# picboard.net
KiCad netlist of a schematic drawn in EAGLE
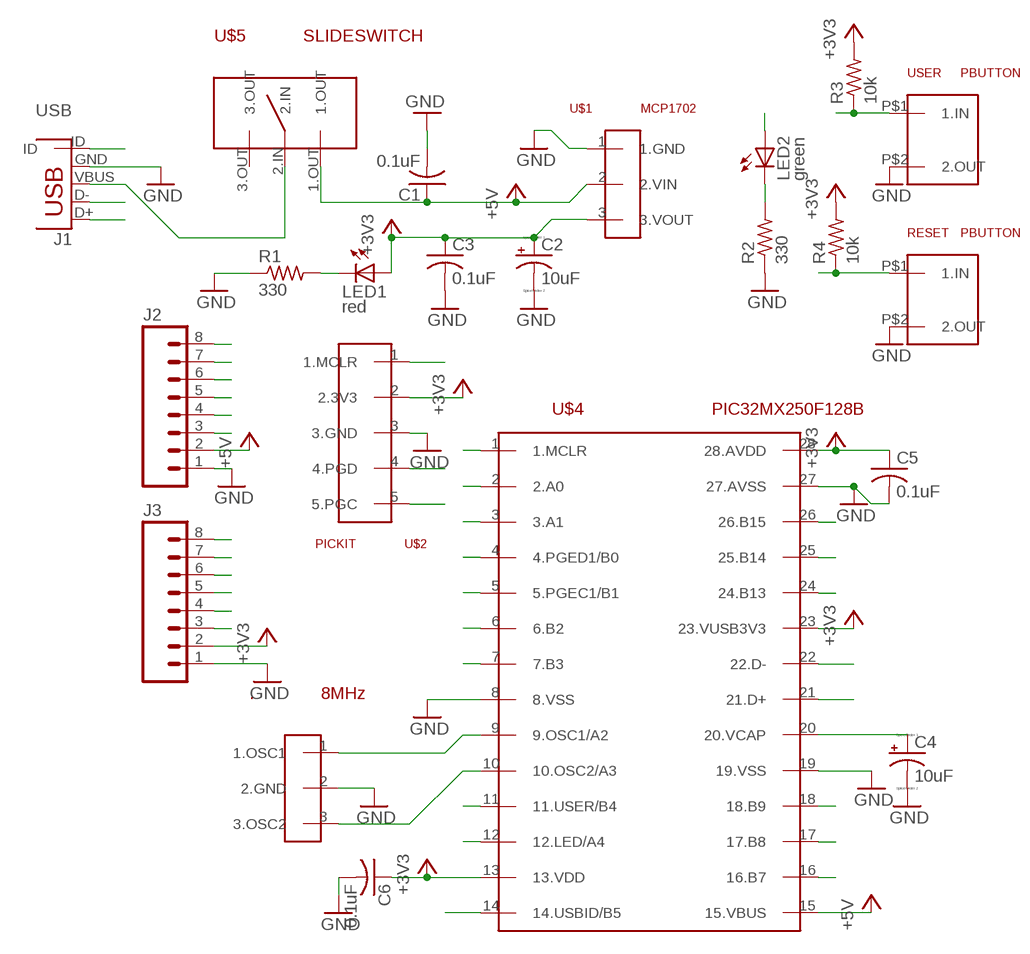
[diagram p0: schematic, sheet 1]

(export (version "E")
  (design (tool "Eeschema 10.0.6"))
  (components
    (comp (ref ".")
      (value "8MHz")
      (footprint "eagle-import:1X03")
      (libsource (lib "eagle-import") (part "OSCIL"))
    )
    (comp (ref "C1")
      (value "0.1uF")
      (footprint "eagle-import:C025-025X050")
      (libsource (lib "eagle-import") (part "C-US025-025X050"))
    )
    (comp (ref "C2")
      (value "10uF")
      (footprint "eagle-import:B45181A")
      (libsource (lib "eagle-import") (part "CPOL-USB45181A"))
    )
    (comp (ref "C3")
      (value "0.1uF")
      (footprint "eagle-import:C025-025X050")
      (libsource (lib "eagle-import") (part "C-US025-025X050"))
    )
    (comp (ref "C4")
      (value "10uF")
      (footprint "eagle-import:B45181A")
      (libsource (lib "eagle-import") (part "CPOL-USB45181A"))
    )
    (comp (ref "C5")
      (value "0.1uF")
      (footprint "eagle-import:C025-025X050")
      (libsource (lib "eagle-import") (part "C-US025-025X050"))
    )
    (comp (ref "C6")
      (value "0.1uF")
      (footprint "eagle-import:C025-025X050")
      (libsource (lib "eagle-import") (part "C-US025-025X050"))
    )
    (comp (ref "J1")
      (value "USB")
      (footprint "eagle-import:USB-MB-H")
      (libsource (lib "eagle-import") (part "USB"))
    )
    (comp (ref "J2")
      (value "M08")
      (footprint "eagle-import:1X08_ROUND")
      (libsource (lib "eagle-import") (part "M08"))
    )
    (comp (ref "J3")
      (value "M08")
      (footprint "eagle-import:1X08_ROUND")
      (libsource (lib "eagle-import") (part "M08"))
    )
    (comp (ref "LED1")
      (value "red")
      (footprint "eagle-import:LED3MM")
      (libsource (lib "eagle-import") (part "LED3MM"))
    )
    (comp (ref "LED2")
      (value "green")
      (footprint "eagle-import:LED3MM")
      (libsource (lib "eagle-import") (part "LED3MM"))
    )
    (comp (ref "R1")
      (value "330")
      (footprint "eagle-import:0207_10")
      (libsource (lib "eagle-import") (part "R-US_0207/10"))
    )
    (comp (ref "R2")
      (value "330")
      (footprint "eagle-import:0207_10")
      (libsource (lib "eagle-import") (part "R-US_0207/10"))
    )
    (comp (ref "R3")
      (value "10k")
      (footprint "eagle-import:0207_10")
      (libsource (lib "eagle-import") (part "R-US_0207/10"))
    )
    (comp (ref "R4")
      (value "10k")
      (footprint "eagle-import:0207_10")
      (libsource (lib "eagle-import") (part "R-US_0207/10"))
    )
    (comp (ref "RESET")
      (value "PBUTTON")
      (footprint "eagle-import:PBUTTON")
      (libsource (lib "eagle-import") (part "PBUTTON"))
    )
    (comp (ref "U$1")
      (value "MCP1702")
      (footprint "eagle-import:TO92")
      (libsource (lib "eagle-import") (part "MCP1702"))
    )
    (comp (ref "U$2")
      (value "PICKIT")
      (footprint "eagle-import:1X05")
      (libsource (lib "eagle-import") (part "PICKIT"))
    )
    (comp (ref "U$4")
      (value "PIC32MX250F128B")
      (footprint "eagle-import:DIL28-3")
      (libsource (lib "eagle-import") (part "PIC32MX250F128B"))
    )
    (comp (ref "U$5")
      (value "SLIDESWITCH")
      (footprint "eagle-import:SLIDESWITCH")
      (libsource (lib "eagle-import") (part "SLIDESWITCH"))
    )
    (comp (ref "USER")
      (value "PBUTTON")
      (footprint "eagle-import:PBUTTON")
      (libsource (lib "eagle-import") (part "PBUTTON"))
    )
  )
  (nets
    (net (code "1") (name "+3V3") (class "Default")
      (node (ref "C2") (pin "+") (pinfunction "+_+") (pintype "passive"))
      (node (ref "C3") (pin "1") (pinfunction "1_1") (pintype "passive"))
      (node (ref "C5") (pin "1") (pinfunction "1_1") (pintype "passive"))
      (node (ref "C6") (pin "1") (pinfunction "1_1") (pintype "passive"))
      (node (ref "J3") (pin "2") (pinfunction "2_2") (pintype "passive"))
      (node (ref "LED1") (pin "A") (pinfunction "A_A") (pintype "passive"))
      (node (ref "R3") (pin "2") (pinfunction "2_2") (pintype "passive"))
      (node (ref "R4") (pin "2") (pinfunction "2_2") (pintype "passive"))
      (node (ref "U$1") (pin "3") (pinfunction "3.VOUT_3") (pintype "bidirectional"))
      (node (ref "U$2") (pin "2") (pinfunction "2.3V3_2") (pintype "bidirectional"))
      (node (ref "U$4") (pin "13") (pinfunction "13.VDD_13") (pintype "bidirectional"))
      (node (ref "U$4") (pin "23") (pinfunction "23.VUSB3V3_23") (pintype "bidirectional"))
      (node (ref "U$4") (pin "28") (pinfunction "28.AVDD_28") (pintype "bidirectional"))
    )
    (net (code "2") (name "+5V") (class "Default")
      (node (ref "C1") (pin "1") (pinfunction "1_1") (pintype "passive"))
      (node (ref "J2") (pin "2") (pinfunction "2_2") (pintype "passive"))
      (node (ref "U$1") (pin "2") (pinfunction "2.VIN_2") (pintype "bidirectional"))
      (node (ref "U$4") (pin "15") (pinfunction "15.VBUS_15") (pintype "bidirectional"))
      (node (ref "U$5") (pin "1.OUT") (pinfunction "1.OUT_1.OUT") (pintype "bidirectional"))
    )
    (net (code "3") (name "/A0") (class "Default")
      (node (ref "J3") (pin "8") (pinfunction "8_8") (pintype "passive"))
      (node (ref "U$4") (pin "2") (pinfunction "2.A0_2") (pintype "bidirectional"))
    )
    (net (code "4") (name "/A1") (class "Default")
      (node (ref "J3") (pin "7") (pinfunction "7_7") (pintype "passive"))
      (node (ref "U$4") (pin "3") (pinfunction "3.A1_3") (pintype "bidirectional"))
    )
    (net (code "5") (name "/B2") (class "Default")
      (node (ref "J3") (pin "6") (pinfunction "6_6") (pintype "passive"))
      (node (ref "U$4") (pin "6") (pinfunction "6.B2_6") (pintype "bidirectional"))
    )
    (net (code "6") (name "/B3") (class "Default")
      (node (ref "J3") (pin "5") (pinfunction "5_5") (pintype "passive"))
      (node (ref "U$4") (pin "7") (pinfunction "7.B3_7") (pintype "bidirectional"))
    )
    (net (code "7") (name "/B7") (class "Default")
      (node (ref "J2") (pin "3") (pinfunction "3_3") (pintype "passive"))
      (node (ref "U$4") (pin "16") (pinfunction "16.B7_16") (pintype "bidirectional"))
    )
    (net (code "8") (name "/B8") (class "Default")
      (node (ref "J2") (pin "4") (pinfunction "4_4") (pintype "passive"))
      (node (ref "U$4") (pin "17") (pinfunction "17.B8_17") (pintype "bidirectional"))
    )
    (net (code "9") (name "/B9") (class "Default")
      (node (ref "J2") (pin "5") (pinfunction "5_5") (pintype "passive"))
      (node (ref "U$4") (pin "18") (pinfunction "18.B9_18") (pintype "bidirectional"))
    )
    (net (code "10") (name "/B13") (class "Default")
      (node (ref "J2") (pin "6") (pinfunction "6_6") (pintype "passive"))
      (node (ref "U$4") (pin "24") (pinfunction "24.B13_24") (pintype "bidirectional"))
    )
    (net (code "11") (name "/B14") (class "Default")
      (node (ref "J2") (pin "7") (pinfunction "7_7") (pintype "passive"))
      (node (ref "U$4") (pin "25") (pinfunction "25.B14_25") (pintype "bidirectional"))
    )
    (net (code "12") (name "/B15") (class "Default")
      (node (ref "J2") (pin "8") (pinfunction "8_8") (pintype "passive"))
      (node (ref "U$4") (pin "26") (pinfunction "26.B15_26") (pintype "bidirectional"))
    )
    (net (code "13") (name "/D+") (class "Default")
      (node (ref "J1") (pin "D+") (pinfunction "D+_D+") (pintype "bidirectional"))
      (node (ref "U$4") (pin "21") (pinfunction "21.D+_21") (pintype "bidirectional"))
    )
    (net (code "14") (name "/D-") (class "Default")
      (node (ref "J1") (pin "D-") (pinfunction "D-_D-") (pintype "bidirectional"))
      (node (ref "U$4") (pin "22") (pinfunction "22.D-_22") (pintype "bidirectional"))
    )
    (net (code "15") (name "/LED{slash}A4") (class "Default")
      (node (ref "J3") (pin "3") (pinfunction "3_3") (pintype "passive"))
      (node (ref "LED2") (pin "A") (pinfunction "A_A") (pintype "passive"))
      (node (ref "U$4") (pin "12") (pinfunction "12.LED/A4_12") (pintype "bidirectional"))
    )
    (net (code "16") (name "/MCLR") (class "Default")
      (node (ref "R4") (pin "1") (pinfunction "1_1") (pintype "passive"))
      (node (ref "RESET") (pin "P$1") (pinfunction "1.IN_P$1") (pintype "bidirectional"))
      (node (ref "U$2") (pin "1") (pinfunction "1.MCLR_1") (pintype "bidirectional"))
      (node (ref "U$4") (pin "1") (pinfunction "1.MCLR_1") (pintype "bidirectional"))
    )
    (net (code "17") (name "/PGC") (class "Default")
      (node (ref "U$2") (pin "5") (pinfunction "5.PGC_5") (pintype "bidirectional"))
      (node (ref "U$4") (pin "5") (pinfunction "5.PGEC1/B1_5") (pintype "bidirectional"))
    )
    (net (code "18") (name "/PGD") (class "Default")
      (node (ref "U$2") (pin "4") (pinfunction "4.PGD_4") (pintype "bidirectional"))
      (node (ref "U$4") (pin "4") (pinfunction "4.PGED1/B0_4") (pintype "bidirectional"))
    )
    (net (code "19") (name "/USBID") (class "Default")
      (node (ref "J1") (pin "ID") (pinfunction "ID_ID") (pintype "bidirectional"))
      (node (ref "U$4") (pin "14") (pinfunction "14.USBID/B5_14") (pintype "bidirectional"))
    )
    (net (code "20") (name "/USER{slash}B4") (class "Default")
      (node (ref "J3") (pin "4") (pinfunction "4_4") (pintype "passive"))
      (node (ref "R3") (pin "1") (pinfunction "1_1") (pintype "passive"))
      (node (ref "U$4") (pin "11") (pinfunction "11.USER/B4_11") (pintype "bidirectional"))
      (node (ref "USER") (pin "P$1") (pinfunction "1.IN_P$1") (pintype "bidirectional"))
    )
    (net (code "21") (name "GND") (class "Default")
      (node (ref ".") (pin "2") (pinfunction "2.GND_2") (pintype "bidirectional"))
      (node (ref "C1") (pin "2") (pinfunction "2_2") (pintype "passive"))
      (node (ref "C2") (pin "-") (pinfunction "-_-") (pintype "passive"))
      (node (ref "C3") (pin "2") (pinfunction "2_2") (pintype "passive"))
      (node (ref "C4") (pin "-") (pinfunction "-_-") (pintype "passive"))
      (node (ref "C5") (pin "2") (pinfunction "2_2") (pintype "passive"))
      (node (ref "C6") (pin "2") (pinfunction "2_2") (pintype "passive"))
      (node (ref "J1") (pin "GND") (pinfunction "GND_GND") (pintype "bidirectional"))
      (node (ref "J2") (pin "1") (pinfunction "1_1") (pintype "passive"))
      (node (ref "J3") (pin "1") (pinfunction "1_1") (pintype "passive"))
      (node (ref "R1") (pin "1") (pinfunction "1_1") (pintype "passive"))
      (node (ref "R2") (pin "1") (pinfunction "1_1") (pintype "passive"))
      (node (ref "RESET") (pin "P$2") (pinfunction "2.OUT_P$2") (pintype "bidirectional"))
      (node (ref "U$1") (pin "1") (pinfunction "1.GND_1") (pintype "bidirectional"))
      (node (ref "U$2") (pin "3") (pinfunction "3.GND_3") (pintype "bidirectional"))
      (node (ref "U$4") (pin "19") (pinfunction "19.VSS_19") (pintype "bidirectional"))
      (node (ref "U$4") (pin "27") (pinfunction "27.AVSS_27") (pintype "bidirectional"))
      (node (ref "U$4") (pin "8") (pinfunction "8.VSS_8") (pintype "bidirectional"))
      (node (ref "USER") (pin "P$2") (pinfunction "2.OUT_P$2") (pintype "bidirectional"))
    )
    (net (code "22") (name "Net-(.-1.OSC1)") (class "Default")
      (node (ref ".") (pin "1") (pinfunction "1.OSC1_1") (pintype "bidirectional"))
      (node (ref "U$4") (pin "9") (pinfunction "9.OSC1/A2_9") (pintype "bidirectional"))
    )
    (net (code "23") (name "Net-(.-3.OSC2)") (class "Default")
      (node (ref ".") (pin "3") (pinfunction "3.OSC2_3") (pintype "bidirectional"))
      (node (ref "U$4") (pin "10") (pinfunction "10.OSC2/A3_10") (pintype "bidirectional"))
    )
    (net (code "24") (name "Net-(J1-PadVBUS)") (class "Default")
      (node (ref "J1") (pin "VBUS") (pinfunction "VBUS_VBUS") (pintype "bidirectional"))
      (node (ref "U$5") (pin "2.IN") (pinfunction "2.IN_2.IN") (pintype "bidirectional"))
    )
    (net (code "25") (name "Net-(LED1-C)") (class "Default")
      (node (ref "LED1") (pin "K") (pinfunction "C_K") (pintype "passive"))
      (node (ref "R1") (pin "2") (pinfunction "2_2") (pintype "passive"))
    )
    (net (code "26") (name "Net-(LED2-C)") (class "Default")
      (node (ref "LED2") (pin "K") (pinfunction "C_K") (pintype "passive"))
      (node (ref "R2") (pin "2") (pinfunction "2_2") (pintype "passive"))
    )
    (net (code "27") (name "Net-(U$4-20.VCAP)") (class "Default")
      (node (ref "C4") (pin "+") (pinfunction "+_+") (pintype "passive"))
      (node (ref "U$4") (pin "20") (pinfunction "20.VCAP_20") (pintype "bidirectional"))
    )
    (net (code "28") (name "unconnected-(U$5-Pad3.OUT)") (class "Default")
      (node (ref "U$5") (pin "3.OUT") (pinfunction "3.OUT_3.OUT") (pintype "bidirectional"))
    )
  )
)
